# SSB_Transceiver_Power_Amplifier.net
KiCad netlist of a schematic drawn in EAGLE
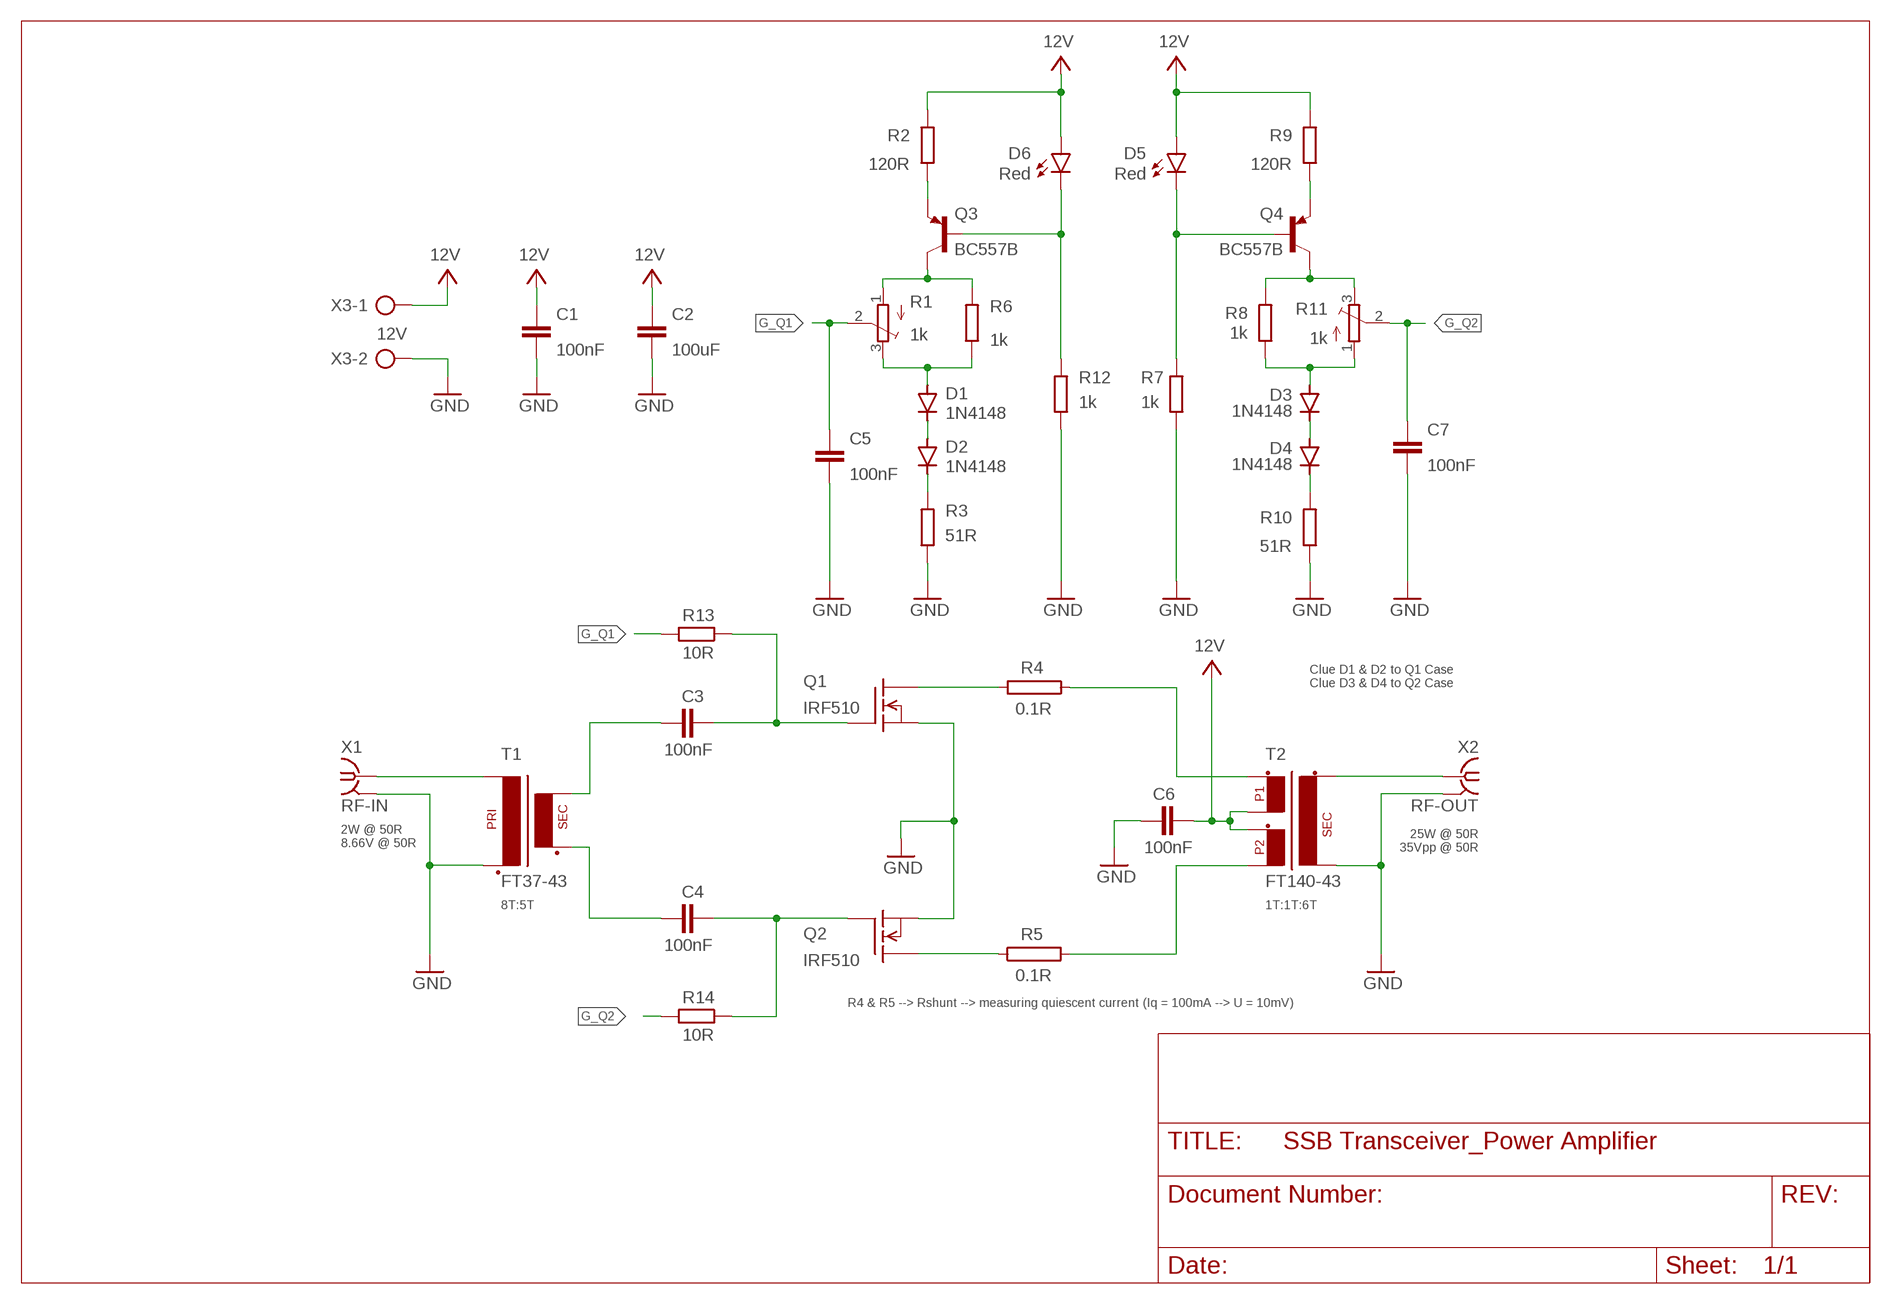
[diagram p0: schematic, sheet 1]

(export (version "E")
  (design (tool "Eeschema 10.0.6"))
  (components
    (comp (ref "C1")
      (value "100nF")
      (footprint "eagle-import:C0805")
      (libsource (lib "eagle-import") (part "C-EUC0805"))
    )
    (comp (ref "C2")
      (value "100uF")
      (footprint "eagle-import:C0805")
      (libsource (lib "eagle-import") (part "C-EUC0805"))
    )
    (comp (ref "C3")
      (value "100nF")
      (footprint "eagle-import:C0805")
      (libsource (lib "eagle-import") (part "C-EUC0805"))
    )
    (comp (ref "C4")
      (value "100nF")
      (footprint "eagle-import:C0805")
      (libsource (lib "eagle-import") (part "C-EUC0805"))
    )
    (comp (ref "C5")
      (value "100nF")
      (footprint "eagle-import:C0805")
      (libsource (lib "eagle-import") (part "C-EUC0805"))
    )
    (comp (ref "C6")
      (value "100nF")
      (footprint "eagle-import:C0805")
      (libsource (lib "eagle-import") (part "C-EUC0805"))
    )
    (comp (ref "C7")
      (value "100nF")
      (footprint "eagle-import:C0805")
      (libsource (lib "eagle-import") (part "C-EUC0805"))
    )
    (comp (ref "D1")
      (value "1N4148")
      (footprint "eagle-import:SOD323-W")
      (libsource (lib "eagle-import") (part "DIODE-SOD323-W"))
    )
    (comp (ref "D2")
      (value "1N4148")
      (footprint "eagle-import:SOD323-W")
      (libsource (lib "eagle-import") (part "DIODE-SOD323-W"))
    )
    (comp (ref "D3")
      (value "1N4148")
      (footprint "eagle-import:SOD323-W")
      (libsource (lib "eagle-import") (part "DIODE-SOD323-W"))
    )
    (comp (ref "D4")
      (value "1N4148")
      (footprint "eagle-import:SOD323-W")
      (libsource (lib "eagle-import") (part "DIODE-SOD323-W"))
    )
    (comp (ref "D5")
      (value "Red")
      (footprint "eagle-import:CHIP-LED0805")
      (libsource (lib "eagle-import") (part "LEDCHIP-LED0805"))
    )
    (comp (ref "D6")
      (value "Red")
      (footprint "eagle-import:CHIP-LED0805")
      (libsource (lib "eagle-import") (part "LEDCHIP-LED0805"))
    )
    (comp (ref "Q1")
      (value "IRF510")
      (footprint "eagle-import:TO220")
      (libsource (lib "eagle-import") (part "IRF510"))
    )
    (comp (ref "Q2")
      (value "IRF510")
      (footprint "eagle-import:TO220")
      (libsource (lib "eagle-import") (part "IRF510"))
    )
    (comp (ref "Q3")
      (value "BC557B")
      (footprint "eagle-import:TO92-EBC")
      (libsource (lib "eagle-import") (part "BC557B"))
    )
    (comp (ref "Q4")
      (value "BC557B")
      (footprint "eagle-import:TO92-EBC")
      (libsource (lib "eagle-import") (part "BC557B"))
    )
    (comp (ref "R1")
      (value "1k")
      (footprint "eagle-import:3223G")
      (libsource (lib "eagle-import") (part "TRIM_EU-3223G"))
    )
    (comp (ref "R2")
      (value "120R")
      (footprint "eagle-import:R0805")
      (libsource (lib "eagle-import") (part "R-EU_R0805"))
    )
    (comp (ref "R3")
      (value "51R")
      (footprint "eagle-import:R0805")
      (libsource (lib "eagle-import") (part "R-EU_R0805"))
    )
    (comp (ref "R4")
      (value "0.1R")
      (footprint "eagle-import:MNS-5")
      (libsource (lib "eagle-import") (part "RMNS-5"))
    )
    (comp (ref "R5")
      (value "0.1R")
      (footprint "eagle-import:MNS-5")
      (libsource (lib "eagle-import") (part "RMNS-5"))
    )
    (comp (ref "R6")
      (value "1k")
      (footprint "eagle-import:R0805")
      (libsource (lib "eagle-import") (part "R-EU_R0805"))
    )
    (comp (ref "R7")
      (value "1k")
      (footprint "eagle-import:R0805")
      (libsource (lib "eagle-import") (part "R-EU_R0805"))
    )
    (comp (ref "R8")
      (value "1k")
      (footprint "eagle-import:R0805")
      (libsource (lib "eagle-import") (part "R-EU_R0805"))
    )
    (comp (ref "R9")
      (value "120R")
      (footprint "eagle-import:R0805")
      (libsource (lib "eagle-import") (part "R-EU_R0805"))
    )
    (comp (ref "R10")
      (value "51R")
      (footprint "eagle-import:R0805")
      (libsource (lib "eagle-import") (part "R-EU_R0805"))
    )
    (comp (ref "R11")
      (value "1k")
      (footprint "eagle-import:3223G")
      (libsource (lib "eagle-import") (part "TRIM_EU-3223G"))
    )
    (comp (ref "R12")
      (value "1k")
      (footprint "eagle-import:R0805")
      (libsource (lib "eagle-import") (part "R-EU_R0805"))
    )
    (comp (ref "R13")
      (value "10R")
      (footprint "eagle-import:R0805")
      (libsource (lib "eagle-import") (part "R-EU_R0805"))
    )
    (comp (ref "R14")
      (value "10R")
      (footprint "eagle-import:R0805")
      (libsource (lib "eagle-import") (part "R-EU_R0805"))
    )
    (comp (ref "T1")
      (value "FT37-43")
      (footprint "eagle-import:FT37-43SMD")
      (libsource (lib "eagle-import") (part "FT37-43"))
    )
    (comp (ref "T2")
      (value "FT140-43")
      (footprint "eagle-import:FT37-43CENTERTAPSMD")
      (libsource (lib "eagle-import") (part "FT37-43CENTERTAP"))
    )
    (comp (ref "X1")
      (value "RF-IN")
      (footprint "eagle-import:J502-ND-142-0711-821_826")
      (fields (field (name "MF") "JOHNSON COMPONENTS") (field (name "MPN") "142-0711-821"))
      (libsource (lib "eagle-import") (part "SMA-PCB-CON142-0711-821/826"))
    )
    (comp (ref "X2")
      (value "RF-OUT")
      (footprint "eagle-import:J502-ND-142-0711-821_826")
      (fields (field (name "MF") "JOHNSON COMPONENTS") (field (name "MPN") "142-0711-821"))
      (libsource (lib "eagle-import") (part "SMA-PCB-CON142-0711-821/826"))
    )
    (comp (ref "X3")
      (value "12V")
      (footprint "eagle-import:AK300_2")
      (libsource (lib "eagle-import") (part "AK300/2"))
    )
  )
  (nets
    (net (code "1") (name "12V") (class "Default")
      (node (ref "C1") (pin "2") (pinfunction "2_2") (pintype "passive"))
      (node (ref "C2") (pin "2") (pinfunction "2_2") (pintype "passive"))
      (node (ref "C6") (pin "2") (pinfunction "2_2") (pintype "passive"))
      (node (ref "D5") (pin "A") (pinfunction "A_A") (pintype "passive"))
      (node (ref "D6") (pin "A") (pinfunction "A_A") (pintype "passive"))
      (node (ref "R2") (pin "2") (pinfunction "2_2") (pintype "passive"))
      (node (ref "R9") (pin "2") (pinfunction "2_2") (pintype "passive"))
      (node (ref "T2") (pin "P$2") (pinfunction "P1_2_P$2") (pintype "passive"))
      (node (ref "T2") (pin "P$3") (pinfunction "P2_1_P$3") (pintype "passive"))
      (node (ref "X3") (pin "1") (pinfunction "KL_1") (pintype "passive"))
    )
    (net (code "2") (name "GND") (class "Default")
      (node (ref "C1") (pin "1") (pinfunction "1_1") (pintype "passive"))
      (node (ref "C2") (pin "1") (pinfunction "1_1") (pintype "passive"))
      (node (ref "C5") (pin "1") (pinfunction "1_1") (pintype "passive"))
      (node (ref "C6") (pin "1") (pinfunction "1_1") (pintype "passive"))
      (node (ref "C7") (pin "1") (pinfunction "1_1") (pintype "passive"))
      (node (ref "Q1") (pin "3") (pinfunction "S_3") (pintype "passive"))
      (node (ref "Q2") (pin "3") (pinfunction "S_3") (pintype "passive"))
      (node (ref "R10") (pin "1") (pinfunction "1_1") (pintype "passive"))
      (node (ref "R12") (pin "1") (pinfunction "1_1") (pintype "passive"))
      (node (ref "R3") (pin "1") (pinfunction "1_1") (pintype "passive"))
      (node (ref "R7") (pin "1") (pinfunction "1_1") (pintype "passive"))
      (node (ref "T1") (pin "P$2") (pinfunction "P2_P$2") (pintype "passive"))
      (node (ref "T2") (pin "S$2") (pinfunction "S2_S$2") (pintype "passive"))
      (node (ref "X1") (pin "G@1") (pinfunction "2_G@1") (pintype "passive"))
      (node (ref "X1") (pin "G@2") (pinfunction "2_G@2") (pintype "passive"))
      (node (ref "X1") (pin "G@3") (pinfunction "2_G@3") (pintype "passive"))
      (node (ref "X1") (pin "G@4") (pinfunction "2_G@4") (pintype "passive"))
      (node (ref "X2") (pin "G@1") (pinfunction "2_G@1") (pintype "passive"))
      (node (ref "X2") (pin "G@2") (pinfunction "2_G@2") (pintype "passive"))
      (node (ref "X2") (pin "G@3") (pinfunction "2_G@3") (pintype "passive"))
      (node (ref "X2") (pin "G@4") (pinfunction "2_G@4") (pintype "passive"))
      (node (ref "X3") (pin "2") (pinfunction "KL_2") (pintype "passive"))
    )
    (net (code "3") (name "G_Q1") (class "Default")
      (node (ref "C5") (pin "2") (pinfunction "2_2") (pintype "passive"))
      (node (ref "R1") (pin "2") (pinfunction "S_2") (pintype "passive"))
      (node (ref "R13") (pin "2") (pinfunction "2_2") (pintype "passive"))
    )
    (net (code "4") (name "G_Q2") (class "Default")
      (node (ref "C7") (pin "2") (pinfunction "2_2") (pintype "passive"))
      (node (ref "R11") (pin "2") (pinfunction "S_2") (pintype "passive"))
      (node (ref "R14") (pin "2") (pinfunction "2_2") (pintype "passive"))
    )
    (net (code "5") (name "Net-(D1-PadC)") (class "Default")
      (node (ref "D1") (pin "C") (pinfunction "C_C") (pintype "passive"))
      (node (ref "D2") (pin "A") (pinfunction "A_A") (pintype "passive"))
    )
    (net (code "6") (name "Net-(D2-PadC)") (class "Default")
      (node (ref "D2") (pin "C") (pinfunction "C_C") (pintype "passive"))
      (node (ref "R3") (pin "2") (pinfunction "2_2") (pintype "passive"))
    )
    (net (code "7") (name "Net-(D3-PadC)") (class "Default")
      (node (ref "D3") (pin "C") (pinfunction "C_C") (pintype "passive"))
      (node (ref "D4") (pin "A") (pinfunction "A_A") (pintype "passive"))
    )
    (net (code "8") (name "Net-(D4-PadC)") (class "Default")
      (node (ref "D4") (pin "C") (pinfunction "C_C") (pintype "passive"))
      (node (ref "R10") (pin "2") (pinfunction "2_2") (pintype "passive"))
    )
    (net (code "9") (name "Net-(D5-PadC)") (class "Default")
      (node (ref "D5") (pin "C") (pinfunction "C_C") (pintype "passive"))
      (node (ref "Q4") (pin "B") (pinfunction "B_B") (pintype "passive"))
      (node (ref "R7") (pin "2") (pinfunction "2_2") (pintype "passive"))
    )
    (net (code "10") (name "Net-(D6-PadC)") (class "Default")
      (node (ref "D6") (pin "C") (pinfunction "C_C") (pintype "passive"))
      (node (ref "Q3") (pin "B") (pinfunction "B_B") (pintype "passive"))
      (node (ref "R12") (pin "2") (pinfunction "2_2") (pintype "passive"))
    )
    (net (code "11") (name "Net-(Q1-D)") (class "Default")
      (node (ref "Q1") (pin "2") (pinfunction "D_2") (pintype "passive"))
      (node (ref "R4") (pin "2") (pinfunction "2_2") (pintype "passive"))
    )
    (net (code "12") (name "Net-(Q1-G)") (class "Default")
      (node (ref "C3") (pin "1") (pinfunction "1_1") (pintype "passive"))
      (node (ref "Q1") (pin "1") (pinfunction "G_1") (pintype "passive"))
      (node (ref "R13") (pin "1") (pinfunction "1_1") (pintype "passive"))
    )
    (net (code "13") (name "Net-(Q2-D)") (class "Default")
      (node (ref "Q2") (pin "2") (pinfunction "D_2") (pintype "passive"))
      (node (ref "R5") (pin "1") (pinfunction "1_1") (pintype "passive"))
    )
    (net (code "14") (name "Net-(Q2-G)") (class "Default")
      (node (ref "C4") (pin "1") (pinfunction "1_1") (pintype "passive"))
      (node (ref "Q2") (pin "1") (pinfunction "G_1") (pintype "passive"))
      (node (ref "R14") (pin "1") (pinfunction "1_1") (pintype "passive"))
    )
    (net (code "15") (name "Net-(Q3-PadE)") (class "Default")
      (node (ref "Q3") (pin "E") (pinfunction "E_E") (pintype "passive"))
      (node (ref "R2") (pin "1") (pinfunction "1_1") (pintype "passive"))
    )
    (net (code "16") (name "Net-(Q4-PadE)") (class "Default")
      (node (ref "Q4") (pin "E") (pinfunction "E_E") (pintype "passive"))
      (node (ref "R9") (pin "1") (pinfunction "1_1") (pintype "passive"))
    )
    (net (code "17") (name "Net-(R1-A)") (class "Default")
      (node (ref "Q3") (pin "C") (pinfunction "C_C") (pintype "passive"))
      (node (ref "R1") (pin "1") (pinfunction "A_1") (pintype "passive"))
      (node (ref "R6") (pin "2") (pinfunction "2_2") (pintype "passive"))
    )
    (net (code "18") (name "Net-(R1-E)") (class "Default")
      (node (ref "D1") (pin "A") (pinfunction "A_A") (pintype "passive"))
      (node (ref "R1") (pin "3") (pinfunction "E_3") (pintype "passive"))
      (node (ref "R6") (pin "1") (pinfunction "1_1") (pintype "passive"))
    )
    (net (code "19") (name "Net-(R11-A)") (class "Default")
      (node (ref "D3") (pin "A") (pinfunction "A_A") (pintype "passive"))
      (node (ref "R11") (pin "1") (pinfunction "A_1") (pintype "passive"))
      (node (ref "R8") (pin "1") (pinfunction "1_1") (pintype "passive"))
    )
    (net (code "20") (name "Net-(R11-E)") (class "Default")
      (node (ref "Q4") (pin "C") (pinfunction "C_C") (pintype "passive"))
      (node (ref "R11") (pin "3") (pinfunction "E_3") (pintype "passive"))
      (node (ref "R8") (pin "2") (pinfunction "2_2") (pintype "passive"))
    )
    (net (code "21") (name "Net-(T1-P1)") (class "Default")
      (node (ref "T1") (pin "P$1") (pinfunction "P1_P$1") (pintype "passive"))
      (node (ref "X1") (pin "1") (pinfunction "1_1") (pintype "passive"))
    )
    (net (code "22") (name "Net-(T1-S1)") (class "Default")
      (node (ref "C3") (pin "2") (pinfunction "2_2") (pintype "passive"))
      (node (ref "T1") (pin "S$1") (pinfunction "S1_S$1") (pintype "passive"))
    )
    (net (code "23") (name "Net-(T1-S2)") (class "Default")
      (node (ref "C4") (pin "2") (pinfunction "2_2") (pintype "passive"))
      (node (ref "T1") (pin "S$2") (pinfunction "S2_S$2") (pintype "passive"))
    )
    (net (code "24") (name "Net-(T2-P1_1)") (class "Default")
      (node (ref "R4") (pin "1") (pinfunction "1_1") (pintype "passive"))
      (node (ref "T2") (pin "P$1") (pinfunction "P1_1_P$1") (pintype "passive"))
    )
    (net (code "25") (name "Net-(T2-P2_2)") (class "Default")
      (node (ref "R5") (pin "2") (pinfunction "2_2") (pintype "passive"))
      (node (ref "T2") (pin "P$4") (pinfunction "P2_2_P$4") (pintype "passive"))
    )
    (net (code "26") (name "Net-(T2-S1)") (class "Default")
      (node (ref "T2") (pin "S$1") (pinfunction "S1_S$1") (pintype "passive"))
      (node (ref "X2") (pin "1") (pinfunction "1_1") (pintype "passive"))
    )
  )
)
